# RFID.net
KiCad netlist of a schematic drawn in Altium Designer
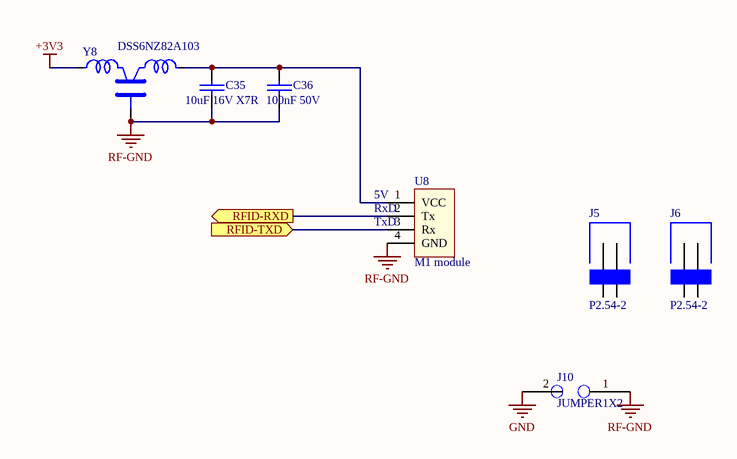
[diagram p0: RFID.SchDoc]

(export (version "E")
  (design (tool "Eeschema 10.0.6"))
  (components
    (comp (ref "C35")
      (value "10uF 16V X7R")
      (footprint "IPC-7352 Chip_Capacitor_N:CAPC3216N")
      (libsource (lib "*") (part "CAP"))
    )
    (comp (ref "C36")
      (value "100nF 50V")
      (footprint "IPC-7352 Chip_Capacitor_N:CAPC2012N")
      (libsource (lib "*") (part "CAP"))
    )
    (comp (ref "J5")
      (value "P2.54-2")
      (footprint "UserPcbLib:JP2-P2.54")
      (libsource (lib "UserSchlib") (part "JP2-2.54"))
    )
    (comp (ref "J6")
      (value "P2.54-2")
      (footprint "UserPcbLib:JP2-P2.54")
      (libsource (lib "UserSchlib") (part "JP2-2.54"))
    )
    (comp (ref "J10")
      (value "JUMPER1X2")
      (footprint "UserPcbLib:JP-SOLDER-H1X2-3X2")
      (libsource (lib "Peter") (part "JUMPER1X2"))
    )
    (comp (ref "U8")
      (value "M1 module")
      (footprint "UserPcbLib:RFID_MOD")
      (description "RFID module")
      (libsource (lib "UserSchlib") (part "RFID-M1"))
    )
    (comp (ref "Y8")
      (value "DSS6NZ82A103")
      (footprint "UserPcbLib:DSS6")
      (description "Murata EMI suppression filter")
      (fields (field (name "MANUFACTURER") "Murata"))
      (libsource (lib "UserSchlib") (part "DSS6"))
    )
  )
  (nets
    (net (code "1") (name "+3V3") (class "Default")
      (node (ref "Y8") (pin "1") (pinfunction "1_1") (pintype "passive"))
    )
    (net (code "2") (name "/RFID-RXD") (class "Default")
      (node (ref "U8") (pin "2") (pinfunction "Tx_2") (pintype "passive"))
    )
    (net (code "3") (name "/RFID-TXD") (class "Default")
      (node (ref "U8") (pin "3") (pinfunction "Rx_3") (pintype "passive"))
    )
    (net (code "4") (name "GND") (class "Default")
      (node (ref "J10") (pin "2") (pinfunction "1_2") (pintype "passive"))
    )
    (net (code "5") (name "Net-(U8-VCC)") (class "Default")
      (node (ref "C35") (pin "1") (pintype "passive"))
      (node (ref "C36") (pin "1") (pintype "passive"))
      (node (ref "U8") (pin "1") (pinfunction "VCC_1") (pintype "passive"))
      (node (ref "Y8") (pin "3") (pinfunction "3_3") (pintype "passive"))
    )
    (net (code "6") (name "RF-GND") (class "Default")
      (node (ref "C35") (pin "2") (pintype "passive"))
      (node (ref "C36") (pin "2") (pintype "passive"))
      (node (ref "J10") (pin "1") (pinfunction "0_1") (pintype "passive"))
      (node (ref "U8") (pin "4") (pinfunction "GND_4") (pintype "passive"))
      (node (ref "Y8") (pin "2") (pinfunction "2_2") (pintype "passive"))
    )
    (net (code "7") (name "unconnected-(J5-Pad1)") (class "Default")
      (node (ref "J5") (pin "1") (pinfunction "1_1") (pintype "power_in"))
    )
    (net (code "8") (name "unconnected-(J5-Pad2)") (class "Default")
      (node (ref "J5") (pin "2") (pinfunction "2_2") (pintype "power_in"))
    )
    (net (code "9") (name "unconnected-(J6-Pad1)") (class "Default")
      (node (ref "J6") (pin "1") (pinfunction "1_1") (pintype "power_in"))
    )
    (net (code "10") (name "unconnected-(J6-Pad2)") (class "Default")
      (node (ref "J6") (pin "2") (pinfunction "2_2") (pintype "power_in"))
    )
  )
)
